# SCH_stc8a8k64s4a12__2021-08-17.net
KiCad netlist of a schematic drawn in EasyEDA
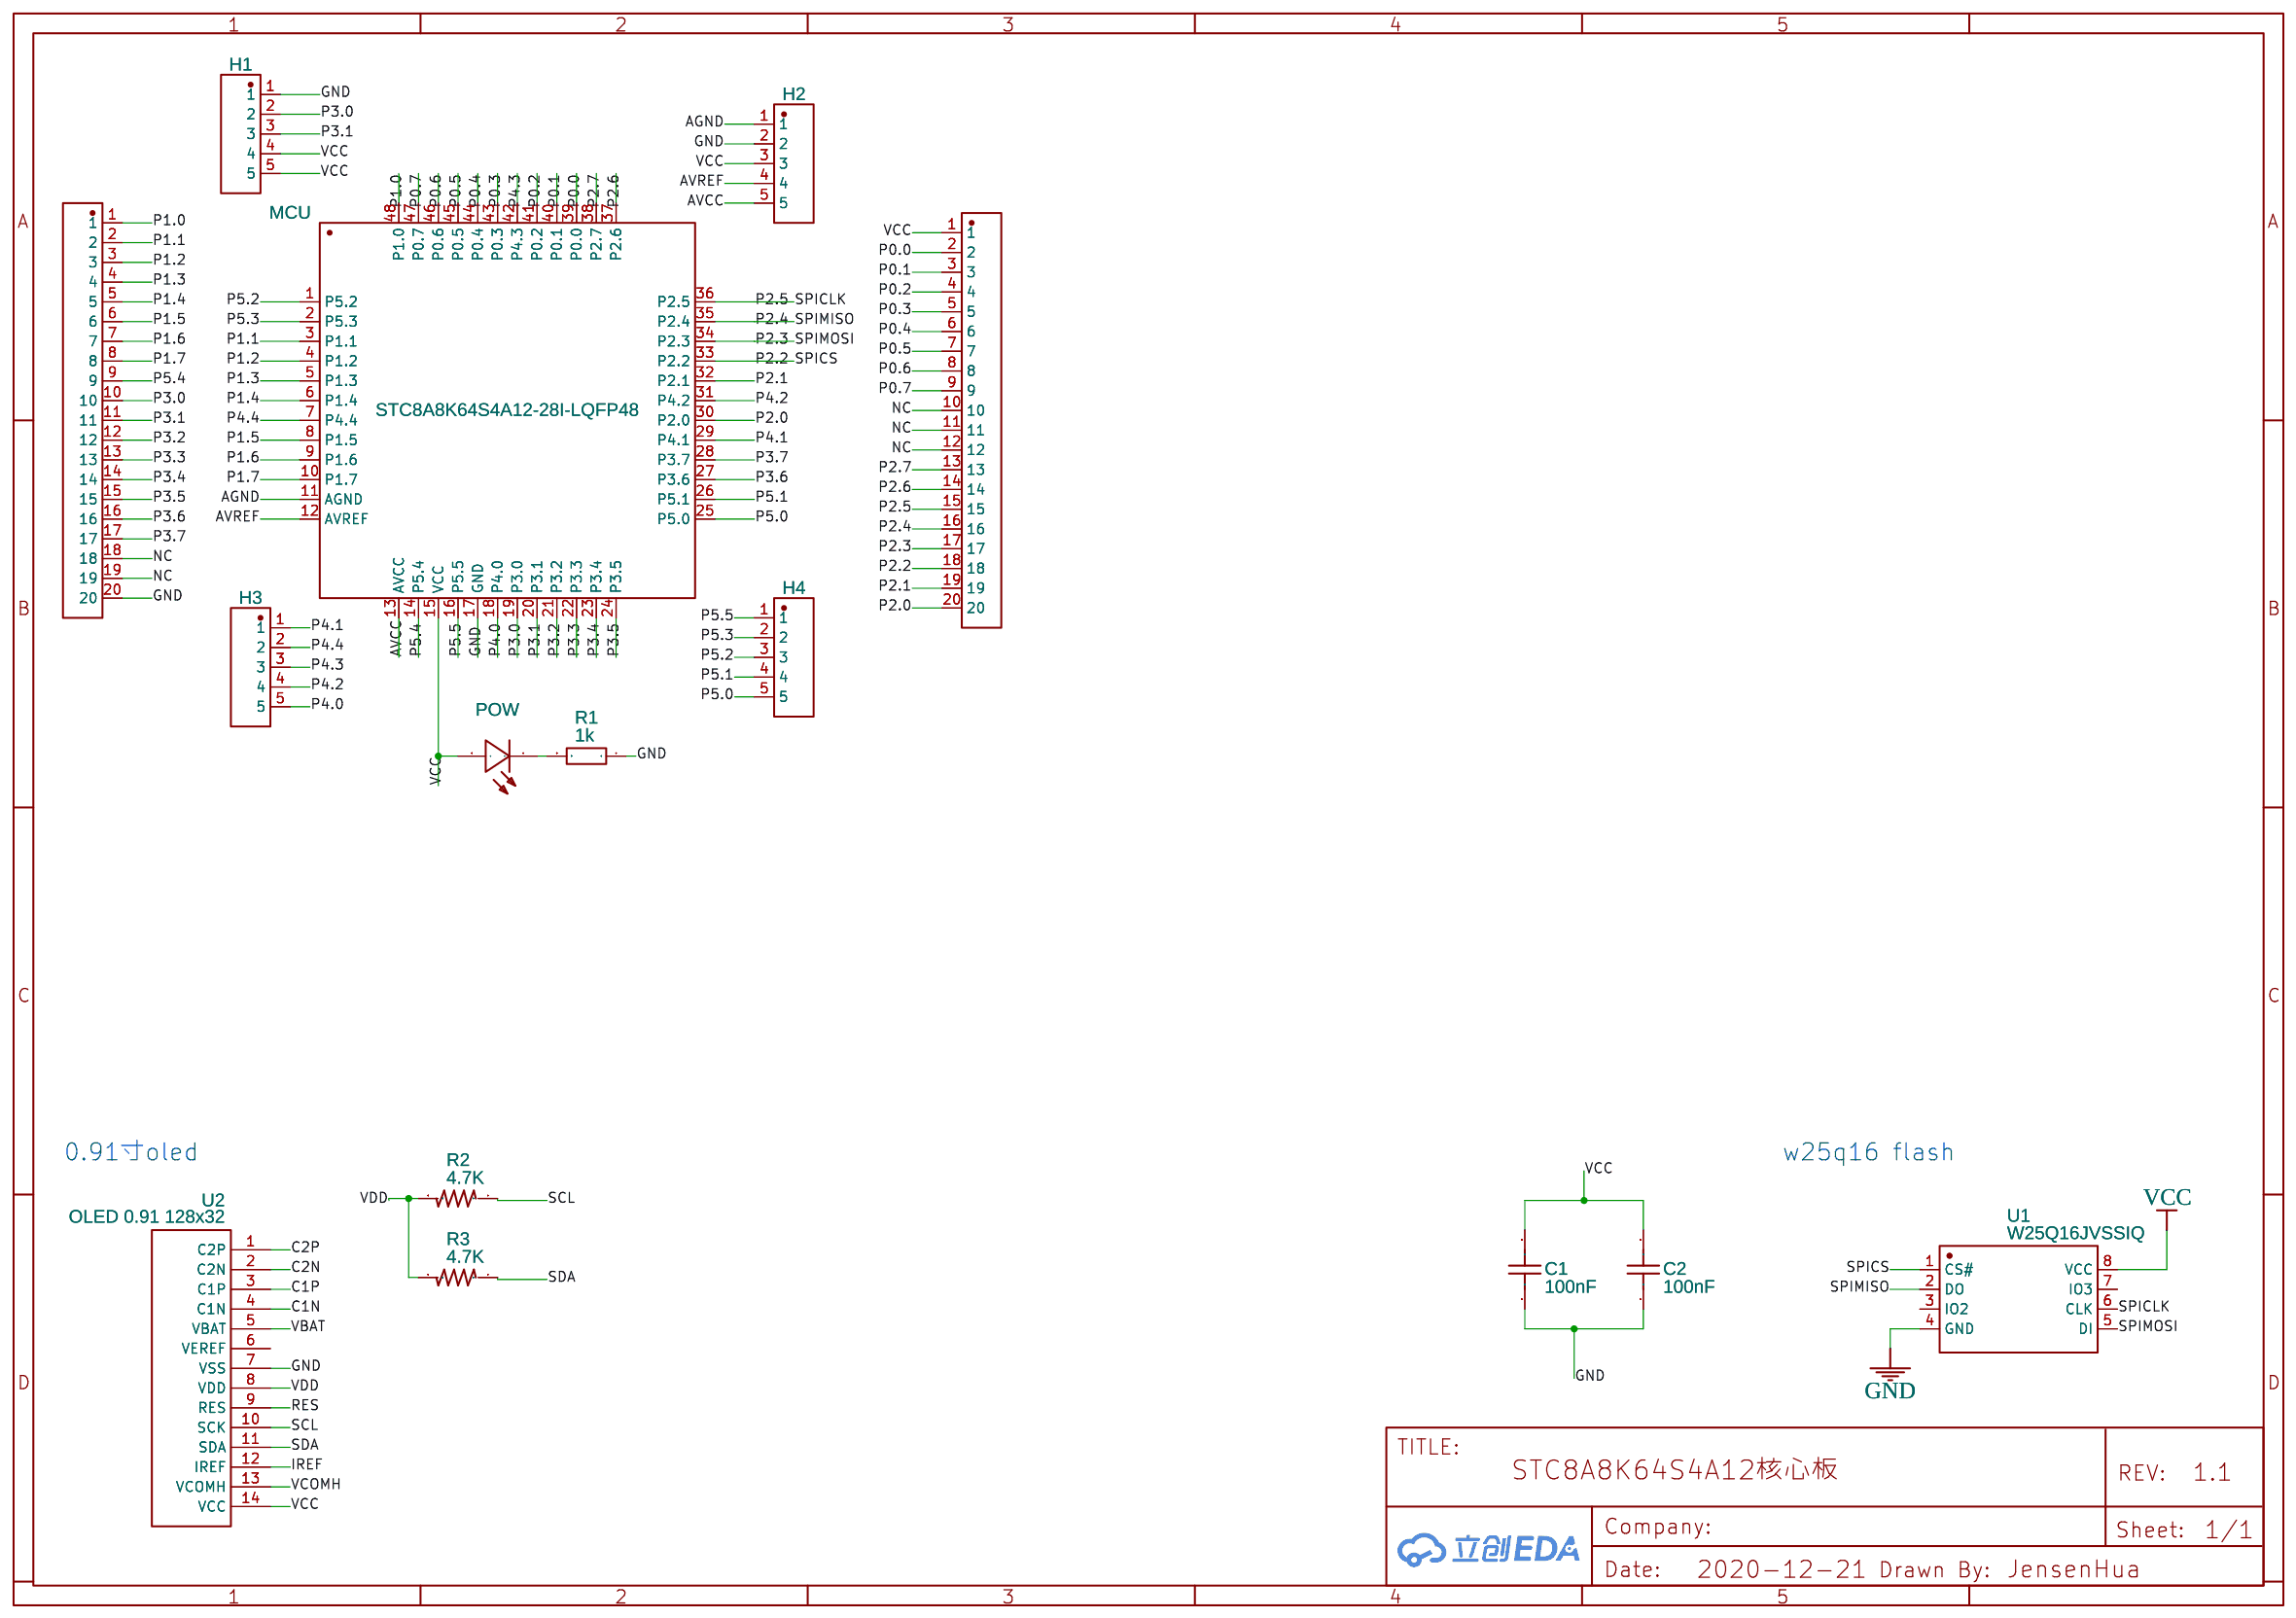
[diagram p0: schematic sheet]

(export (version "E")
  (design (tool "Eeschema 10.0.6"))
  (components
    (comp (ref "C1")
      (value "100nF")
      (fields
        (field (name "BOM_Manufacturer Part") "FM18X104K101PBG")
        (field (name "BOM_Supplier Part") "C525175")
      )
      (libsource (lib "") (part "FM18X104K101PBG"))
    )
    (comp (ref "C2")
      (value "100nF")
      (fields
        (field (name "BOM_Manufacturer Part") "FM18X104K101PBG")
        (field (name "BOM_Supplier Part") "C525175")
      )
      (libsource (lib "") (part "FM18X104K101PBG"))
    )
    (comp (ref "H1")
      (value "2185-105SSNAYNT2")
      (fields (field (name "BOM_Supplier Part") "C721789"))
      (libsource (lib "") (part "2185-105SSNAYNT2_1"))
    )
    (comp (ref "H2")
      (value "2185-105SSNAYNT2")
      (fields (field (name "BOM_Supplier Part") "C721789"))
      (libsource (lib "") (part "2185-105SSNAYNT2"))
    )
    (comp (ref "H3")
      (value "2185-105SSNAYNT2")
      (fields (field (name "BOM_Supplier Part") "C721789"))
      (libsource (lib "") (part "2185-105SSNAYNT2_1"))
    )
    (comp (ref "H4")
      (value "2185-105SSNAYNT2")
      (fields (field (name "BOM_Supplier Part") "C721789"))
      (libsource (lib "") (part "2185-105SSNAYNT2"))
    )
    (comp (ref "J")
      (value "Header-Male-2.54_1x20")
      (fields
        (field (name "BOM_Manufacturer Part") "2.54mm 1*20PHeader")
        (field (name "BOM_Supplier Part") "C50981")
      )
      (libsource (lib "") (part "Header-Male-2.54_1x20_1"))
    )
    (comp (ref "J1")
      (value "Header-Male-2.54_1x20")
      (fields
        (field (name "BOM_Manufacturer Part") "2.54mm 1*20PHeader")
        (field (name "BOM_Supplier Part") "C50981")
      )
      (libsource (lib "") (part "Header-Male-2.54_1x20"))
    )
    (comp (ref "MCU")
      (value "STC8A8K64S4A12-28I-LQFP48")
      (fields
        (field (name "BOM_Manufacturer Part") "STC8A8K64S4A12")
        (field (name "BOM_Supplier Part") "C84390")
      )
      (libsource (lib "") (part "STC8A8K64S4A12_C84390"))
    )
    (comp (ref "POW")
      (value "led Green")
      (fields (field (name "BOM_Supplier Part") "C14641"))
      (libsource (lib "") (part "led Green"))
    )
    (comp (ref "R1")
      (value "1k")
      (fields
        (field (name "BOM_Manufacturer Part") "0603WAF1000T5E")
        (field (name "BOM_Supplier Part") "C22775")
      )
      (libsource (lib "") (part "0603"))
    )
    (comp (ref "R2") (value "4.7K") (libsource (lib "") (part "4.7K")))
    (comp (ref "R3") (value "4.7K") (libsource (lib "") (part "4.7K")))
    (comp (ref "U1")
      (value "W25Q16JVSSIQ")
      (fields
        (field (name "BOM_Manufacturer Part") "W25Q64JVSSIQ")
        (field (name "BOM_Supplier Part") "C83140")
      )
      (libsource (lib "") (part "W25Q64JVSSIQ"))
    )
    (comp (ref "U2") (value "OLED 0.91 128x32") (libsource (lib "") (part "OLED 0.91 128x32")))
  )
  (nets
    (net (code "1") (name "/AGND") (class "Default")
      (node (ref "H2") (pin "1") (pinfunction "1_1") (pintype "unspecified"))
      (node (ref "MCU") (pin "11") (pinfunction "AGND_11") (pintype "unspecified"))
    )
    (net (code "2") (name "/AVCC") (class "Default")
      (node (ref "H2") (pin "5") (pinfunction "5_5") (pintype "unspecified"))
      (node (ref "MCU") (pin "13") (pinfunction "AVCC_13") (pintype "unspecified"))
    )
    (net (code "3") (name "/AVREF") (class "Default")
      (node (ref "H2") (pin "4") (pinfunction "4_4") (pintype "unspecified"))
      (node (ref "MCU") (pin "12") (pinfunction "AVREF_12") (pintype "unspecified"))
    )
    (net (code "4") (name "/C1N") (class "Default")
      (node (ref "U2") (pin "4") (pinfunction "C1N_4") (pintype "unspecified"))
    )
    (net (code "5") (name "/C1P") (class "Default")
      (node (ref "U2") (pin "3") (pinfunction "C1P_3") (pintype "unspecified"))
    )
    (net (code "6") (name "/C2N") (class "Default")
      (node (ref "U2") (pin "2") (pinfunction "C2N_2") (pintype "unspecified"))
    )
    (net (code "7") (name "/C2P") (class "Default")
      (node (ref "U2") (pin "1") (pinfunction "C2P_1") (pintype "unspecified"))
    )
    (net (code "8") (name "/IREF") (class "Default")
      (node (ref "U2") (pin "12") (pinfunction "IREF_12") (pintype "unspecified"))
    )
    (net (code "9") (name "/NC") (class "Default")
      (node (ref "J") (pin "10") (pinfunction "10_10") (pintype "unspecified"))
      (node (ref "J") (pin "11") (pinfunction "11_11") (pintype "unspecified"))
      (node (ref "J") (pin "12") (pinfunction "12_12") (pintype "unspecified"))
      (node (ref "J1") (pin "18") (pinfunction "18_18") (pintype "unspecified"))
      (node (ref "J1") (pin "19") (pinfunction "19_19") (pintype "unspecified"))
    )
    (net (code "10") (name "/P0.0") (class "Default")
      (node (ref "J") (pin "2") (pinfunction "2_2") (pintype "unspecified"))
      (node (ref "MCU") (pin "39") (pinfunction "P0.0_39") (pintype "unspecified"))
    )
    (net (code "11") (name "/P0.1") (class "Default")
      (node (ref "J") (pin "3") (pinfunction "3_3") (pintype "unspecified"))
      (node (ref "MCU") (pin "40") (pinfunction "P0.1_40") (pintype "unspecified"))
    )
    (net (code "12") (name "/P0.2") (class "Default")
      (node (ref "J") (pin "4") (pinfunction "4_4") (pintype "unspecified"))
      (node (ref "MCU") (pin "41") (pinfunction "P0.2_41") (pintype "unspecified"))
    )
    (net (code "13") (name "/P0.3") (class "Default")
      (node (ref "J") (pin "5") (pinfunction "5_5") (pintype "unspecified"))
      (node (ref "MCU") (pin "43") (pinfunction "P0.3_43") (pintype "unspecified"))
    )
    (net (code "14") (name "/P0.4") (class "Default")
      (node (ref "J") (pin "6") (pinfunction "6_6") (pintype "unspecified"))
      (node (ref "MCU") (pin "44") (pinfunction "P0.4_44") (pintype "unspecified"))
    )
    (net (code "15") (name "/P0.5") (class "Default")
      (node (ref "J") (pin "7") (pinfunction "7_7") (pintype "unspecified"))
      (node (ref "MCU") (pin "45") (pinfunction "P0.5_45") (pintype "unspecified"))
    )
    (net (code "16") (name "/P0.6") (class "Default")
      (node (ref "J") (pin "8") (pinfunction "8_8") (pintype "unspecified"))
      (node (ref "MCU") (pin "46") (pinfunction "P0.6_46") (pintype "unspecified"))
    )
    (net (code "17") (name "/P0.7") (class "Default")
      (node (ref "J") (pin "9") (pinfunction "9_9") (pintype "unspecified"))
      (node (ref "MCU") (pin "47") (pinfunction "P0.7_47") (pintype "unspecified"))
    )
    (net (code "18") (name "/P1.0") (class "Default")
      (node (ref "J1") (pin "1") (pinfunction "1_1") (pintype "unspecified"))
      (node (ref "MCU") (pin "48") (pinfunction "P1.0_48") (pintype "unspecified"))
    )
    (net (code "19") (name "/P1.1") (class "Default")
      (node (ref "J1") (pin "2") (pinfunction "2_2") (pintype "unspecified"))
      (node (ref "MCU") (pin "3") (pinfunction "P1.1_3") (pintype "unspecified"))
    )
    (net (code "20") (name "/P1.2") (class "Default")
      (node (ref "J1") (pin "3") (pinfunction "3_3") (pintype "unspecified"))
      (node (ref "MCU") (pin "4") (pinfunction "P1.2_4") (pintype "unspecified"))
    )
    (net (code "21") (name "/P1.3") (class "Default")
      (node (ref "J1") (pin "4") (pinfunction "4_4") (pintype "unspecified"))
      (node (ref "MCU") (pin "5") (pinfunction "P1.3_5") (pintype "unspecified"))
    )
    (net (code "22") (name "/P1.4") (class "Default")
      (node (ref "J1") (pin "5") (pinfunction "5_5") (pintype "unspecified"))
      (node (ref "MCU") (pin "6") (pinfunction "P1.4_6") (pintype "unspecified"))
    )
    (net (code "23") (name "/P1.5") (class "Default")
      (node (ref "J1") (pin "6") (pinfunction "6_6") (pintype "unspecified"))
      (node (ref "MCU") (pin "8") (pinfunction "P1.5_8") (pintype "unspecified"))
    )
    (net (code "24") (name "/P1.6") (class "Default")
      (node (ref "J1") (pin "7") (pinfunction "7_7") (pintype "unspecified"))
      (node (ref "MCU") (pin "9") (pinfunction "P1.6_9") (pintype "unspecified"))
    )
    (net (code "25") (name "/P1.7") (class "Default")
      (node (ref "J1") (pin "8") (pinfunction "8_8") (pintype "unspecified"))
      (node (ref "MCU") (pin "10") (pinfunction "P1.7_10") (pintype "unspecified"))
    )
    (net (code "26") (name "/P2.0") (class "Default")
      (node (ref "J") (pin "20") (pinfunction "20_20") (pintype "unspecified"))
      (node (ref "MCU") (pin "30") (pinfunction "P2.0_30") (pintype "unspecified"))
    )
    (net (code "27") (name "/P2.1") (class "Default")
      (node (ref "J") (pin "19") (pinfunction "19_19") (pintype "unspecified"))
      (node (ref "MCU") (pin "32") (pinfunction "P2.1_32") (pintype "unspecified"))
    )
    (net (code "28") (name "/P2.2") (class "Default")
      (node (ref "J") (pin "18") (pinfunction "18_18") (pintype "unspecified"))
      (node (ref "MCU") (pin "33") (pinfunction "P2.2_33") (pintype "unspecified"))
      (node (ref "U1") (pin "1") (pinfunction "CS#_1") (pintype "unspecified"))
    )
    (net (code "29") (name "/P2.3") (class "Default")
      (node (ref "J") (pin "17") (pinfunction "17_17") (pintype "unspecified"))
      (node (ref "MCU") (pin "34") (pinfunction "P2.3_34") (pintype "unspecified"))
      (node (ref "U1") (pin "5") (pinfunction "DI_5") (pintype "unspecified"))
    )
    (net (code "30") (name "/P2.4") (class "Default")
      (node (ref "J") (pin "16") (pinfunction "16_16") (pintype "unspecified"))
      (node (ref "MCU") (pin "35") (pinfunction "P2.4_35") (pintype "unspecified"))
      (node (ref "U1") (pin "2") (pinfunction "DO_2") (pintype "unspecified"))
    )
    (net (code "31") (name "/P2.5") (class "Default")
      (node (ref "J") (pin "15") (pinfunction "15_15") (pintype "unspecified"))
      (node (ref "MCU") (pin "36") (pinfunction "P2.5_36") (pintype "unspecified"))
      (node (ref "U1") (pin "6") (pinfunction "CLK_6") (pintype "unspecified"))
    )
    (net (code "32") (name "/P2.6") (class "Default")
      (node (ref "J") (pin "14") (pinfunction "14_14") (pintype "unspecified"))
      (node (ref "MCU") (pin "37") (pinfunction "P2.6_37") (pintype "unspecified"))
    )
    (net (code "33") (name "/P2.7") (class "Default")
      (node (ref "J") (pin "13") (pinfunction "13_13") (pintype "unspecified"))
      (node (ref "MCU") (pin "38") (pinfunction "P2.7_38") (pintype "unspecified"))
    )
    (net (code "34") (name "/P3.0") (class "Default")
      (node (ref "H1") (pin "2") (pinfunction "2_2") (pintype "unspecified"))
      (node (ref "J1") (pin "10") (pinfunction "10_10") (pintype "unspecified"))
      (node (ref "MCU") (pin "19") (pinfunction "P3.0_19") (pintype "unspecified"))
    )
    (net (code "35") (name "/P3.1") (class "Default")
      (node (ref "H1") (pin "3") (pinfunction "3_3") (pintype "unspecified"))
      (node (ref "J1") (pin "11") (pinfunction "11_11") (pintype "unspecified"))
      (node (ref "MCU") (pin "20") (pinfunction "P3.1_20") (pintype "unspecified"))
    )
    (net (code "36") (name "/P3.2") (class "Default")
      (node (ref "J1") (pin "12") (pinfunction "12_12") (pintype "unspecified"))
      (node (ref "MCU") (pin "21") (pinfunction "P3.2_21") (pintype "unspecified"))
    )
    (net (code "37") (name "/P3.3") (class "Default")
      (node (ref "J1") (pin "13") (pinfunction "13_13") (pintype "unspecified"))
      (node (ref "MCU") (pin "22") (pinfunction "P3.3_22") (pintype "unspecified"))
    )
    (net (code "38") (name "/P3.4") (class "Default")
      (node (ref "J1") (pin "14") (pinfunction "14_14") (pintype "unspecified"))
      (node (ref "MCU") (pin "23") (pinfunction "P3.4_23") (pintype "unspecified"))
    )
    (net (code "39") (name "/P3.5") (class "Default")
      (node (ref "J1") (pin "15") (pinfunction "15_15") (pintype "unspecified"))
      (node (ref "MCU") (pin "24") (pinfunction "P3.5_24") (pintype "unspecified"))
    )
    (net (code "40") (name "/P3.6") (class "Default")
      (node (ref "J1") (pin "16") (pinfunction "16_16") (pintype "unspecified"))
      (node (ref "MCU") (pin "27") (pinfunction "P3.6_27") (pintype "unspecified"))
    )
    (net (code "41") (name "/P3.7") (class "Default")
      (node (ref "J1") (pin "17") (pinfunction "17_17") (pintype "unspecified"))
      (node (ref "MCU") (pin "28") (pinfunction "P3.7_28") (pintype "unspecified"))
    )
    (net (code "42") (name "/P4.0") (class "Default")
      (node (ref "H3") (pin "5") (pinfunction "5_5") (pintype "unspecified"))
      (node (ref "MCU") (pin "18") (pinfunction "P4.0_18") (pintype "unspecified"))
    )
    (net (code "43") (name "/P4.1") (class "Default")
      (node (ref "H3") (pin "1") (pinfunction "1_1") (pintype "unspecified"))
      (node (ref "MCU") (pin "29") (pinfunction "P4.1_29") (pintype "unspecified"))
    )
    (net (code "44") (name "/P4.2") (class "Default")
      (node (ref "H3") (pin "4") (pinfunction "4_4") (pintype "unspecified"))
      (node (ref "MCU") (pin "31") (pinfunction "P4.2_31") (pintype "unspecified"))
    )
    (net (code "45") (name "/P4.3") (class "Default")
      (node (ref "H3") (pin "3") (pinfunction "3_3") (pintype "unspecified"))
      (node (ref "MCU") (pin "42") (pinfunction "P4.3_42") (pintype "unspecified"))
    )
    (net (code "46") (name "/P4.4") (class "Default")
      (node (ref "H3") (pin "2") (pinfunction "2_2") (pintype "unspecified"))
      (node (ref "MCU") (pin "7") (pinfunction "P4.4_7") (pintype "unspecified"))
    )
    (net (code "47") (name "/P5.0") (class "Default")
      (node (ref "H4") (pin "5") (pinfunction "5_5") (pintype "unspecified"))
      (node (ref "MCU") (pin "25") (pinfunction "P5.0_25") (pintype "unspecified"))
    )
    (net (code "48") (name "/P5.1") (class "Default")
      (node (ref "H4") (pin "4") (pinfunction "4_4") (pintype "unspecified"))
      (node (ref "MCU") (pin "26") (pinfunction "P5.1_26") (pintype "unspecified"))
    )
    (net (code "49") (name "/P5.2") (class "Default")
      (node (ref "H4") (pin "3") (pinfunction "3_3") (pintype "unspecified"))
      (node (ref "MCU") (pin "1") (pinfunction "P5.2_1") (pintype "unspecified"))
    )
    (net (code "50") (name "/P5.3") (class "Default")
      (node (ref "H4") (pin "2") (pinfunction "2_2") (pintype "unspecified"))
      (node (ref "MCU") (pin "2") (pinfunction "P5.3_2") (pintype "unspecified"))
    )
    (net (code "51") (name "/P5.4") (class "Default")
      (node (ref "J1") (pin "9") (pinfunction "9_9") (pintype "unspecified"))
      (node (ref "MCU") (pin "14") (pinfunction "P5.4_14") (pintype "unspecified"))
    )
    (net (code "52") (name "/P5.5") (class "Default")
      (node (ref "H4") (pin "1") (pinfunction "1_1") (pintype "unspecified"))
      (node (ref "MCU") (pin "16") (pinfunction "P5.5_16") (pintype "unspecified"))
    )
    (net (code "53") (name "/RES") (class "Default")
      (node (ref "U2") (pin "9") (pinfunction "RES_9") (pintype "unspecified"))
    )
    (net (code "54") (name "/SCL") (class "Default")
      (node (ref "R2") (pin "1") (pinfunction "1_1") (pintype "unspecified"))
      (node (ref "U2") (pin "10") (pinfunction "SCK_10") (pintype "unspecified"))
    )
    (net (code "55") (name "/SDA") (class "Default")
      (node (ref "R3") (pin "1") (pinfunction "1_1") (pintype "unspecified"))
      (node (ref "U2") (pin "11") (pinfunction "SDA_11") (pintype "unspecified"))
    )
    (net (code "56") (name "/VBAT") (class "Default")
      (node (ref "U2") (pin "5") (pinfunction "VBAT_5") (pintype "unspecified"))
    )
    (net (code "57") (name "/VCOMH") (class "Default")
      (node (ref "U2") (pin "13") (pinfunction "VCOMH_13") (pintype "unspecified"))
    )
    (net (code "58") (name "/VDD") (class "Default")
      (node (ref "R2") (pin "2") (pinfunction "2_2") (pintype "unspecified"))
      (node (ref "R3") (pin "2") (pinfunction "2_2") (pintype "unspecified"))
      (node (ref "U2") (pin "8") (pinfunction "VDD_8") (pintype "unspecified"))
    )
    (net (code "59") (name "GND") (class "Default")
      (node (ref "C1") (pin "1") (pinfunction "1_1") (pintype "unspecified"))
      (node (ref "C2") (pin "1") (pinfunction "1_1") (pintype "unspecified"))
      (node (ref "H1") (pin "1") (pinfunction "1_1") (pintype "unspecified"))
      (node (ref "H2") (pin "2") (pinfunction "2_2") (pintype "unspecified"))
      (node (ref "J1") (pin "20") (pinfunction "20_20") (pintype "unspecified"))
      (node (ref "MCU") (pin "17") (pinfunction "GND_17") (pintype "unspecified"))
      (node (ref "R1") (pin "1") (pinfunction "1_1") (pintype "input"))
      (node (ref "U1") (pin "4") (pinfunction "GND_4") (pintype "unspecified"))
      (node (ref "U2") (pin "7") (pinfunction "VSS_7") (pintype "unspecified"))
    )
    (net (code "60") (name "Net-(POW--)") (class "Default")
      (node (ref "POW") (pin "1") (pinfunction "-_1") (pintype "unspecified"))
      (node (ref "R1") (pin "2") (pinfunction "2_2") (pintype "input"))
    )
    (net (code "61") (name "VCC") (class "Default")
      (node (ref "C1") (pin "2") (pinfunction "2_2") (pintype "unspecified"))
      (node (ref "C2") (pin "2") (pinfunction "2_2") (pintype "unspecified"))
      (node (ref "H1") (pin "4") (pinfunction "4_4") (pintype "unspecified"))
      (node (ref "H1") (pin "5") (pinfunction "5_5") (pintype "unspecified"))
      (node (ref "H2") (pin "3") (pinfunction "3_3") (pintype "unspecified"))
      (node (ref "J") (pin "1") (pinfunction "1_1") (pintype "unspecified"))
      (node (ref "MCU") (pin "15") (pinfunction "VCC_15") (pintype "unspecified"))
      (node (ref "POW") (pin "2") (pinfunction "+_2") (pintype "unspecified"))
      (node (ref "U1") (pin "8") (pinfunction "VCC_8") (pintype "unspecified"))
      (node (ref "U2") (pin "14") (pinfunction "VCC_14") (pintype "unspecified"))
    )
    (net (code "62") (name "unconnected-(U1-IO2-Pad3)") (class "Default")
      (node (ref "U1") (pin "3") (pinfunction "IO2_3") (pintype "unspecified"))
    )
    (net (code "63") (name "unconnected-(U1-IO3-Pad7)") (class "Default")
      (node (ref "U1") (pin "7") (pinfunction "IO3_7") (pintype "unspecified"))
    )
    (net (code "64") (name "unconnected-(U2-VEREF-Pad6)") (class "Default")
      (node (ref "U2") (pin "6") (pinfunction "VEREF_6") (pintype "unspecified"))
    )
  )
)
